# PDM.net
KiCad netlist of a schematic drawn in EAGLE
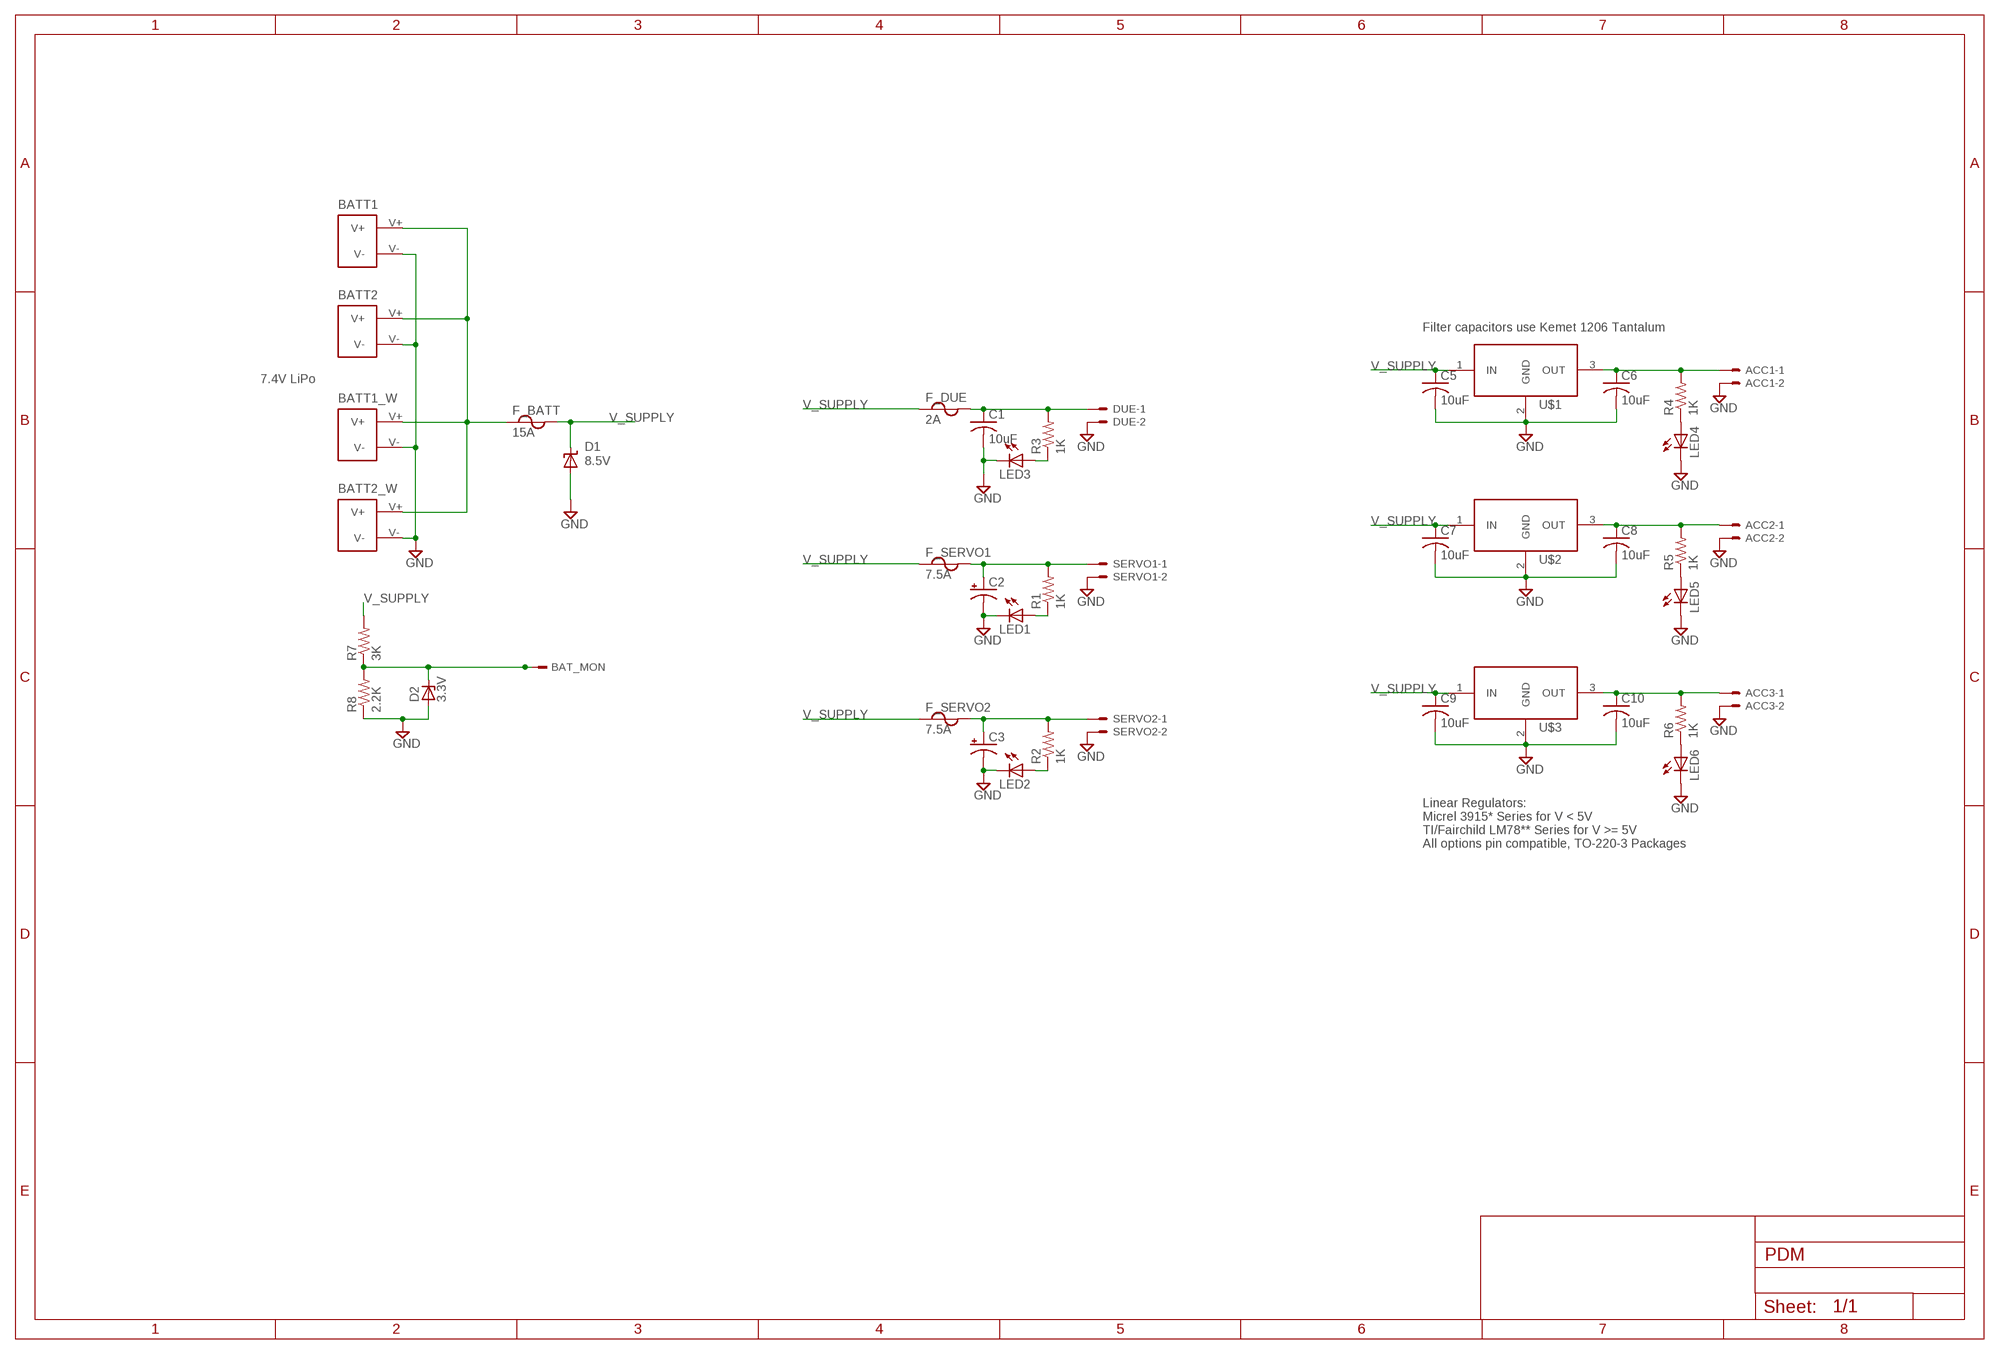
[diagram p0: schematic, sheet 1]

(export (version "E")
  (design (tool "Eeschema 10.0.6"))
  (components
    (comp (ref "ACC1")
      (value "5566-2")
      (footprint "eagle-import:5566-2")
      (libsource (lib "eagle-import") (part "5566-2"))
    )
    (comp (ref "ACC2")
      (value "5566-2")
      (footprint "eagle-import:5566-2")
      (libsource (lib "eagle-import") (part "5566-2"))
    )
    (comp (ref "ACC3")
      (value "5566-2")
      (footprint "eagle-import:5566-2")
      (libsource (lib "eagle-import") (part "5566-2"))
    )
    (comp (ref "BATT1")
      (value "CON_XT60-PCB_MOUNT")
      (footprint "eagle-import:CON_XT60_PCB_MOUNT")
      (libsource (lib "eagle-import") (part "CON_XT60-PCB_MOUNT"))
    )
    (comp (ref "BATT1_W")
      (value "CON_XT60-PIGTAIL")
      (footprint "eagle-import:CON_XT60_PIGTAIL")
      (libsource (lib "eagle-import") (part "CON_XT60-PIGTAIL"))
    )
    (comp (ref "BATT2")
      (value "CON_XT60-PCB_MOUNT")
      (footprint "eagle-import:CON_XT60_PCB_MOUNT")
      (libsource (lib "eagle-import") (part "CON_XT60-PCB_MOUNT"))
    )
    (comp (ref "BATT2_W")
      (value "CON_XT60-PIGTAIL")
      (footprint "eagle-import:CON_XT60_PIGTAIL")
      (libsource (lib "eagle-import") (part "CON_XT60-PIGTAIL"))
    )
    (comp (ref "BAT_MON")
      (value "TSW-101-02-S-S")
      (footprint "eagle-import:TSW-101-02-S-S")
      (libsource (lib "eagle-import") (part "TSW-101-02-S-S"))
    )
    (comp (ref "C1")
      (value "10uF")
      (footprint "eagle-import:C1206K")
      (libsource (lib "eagle-import") (part "C-USC1206K"))
    )
    (comp (ref "C2")
      (value "CPOL-USTT5D11")
      (footprint "eagle-import:TT5D11")
      (libsource (lib "eagle-import") (part "CPOL-USTT5D11"))
    )
    (comp (ref "C3")
      (value "CPOL-USTT5D11")
      (footprint "eagle-import:TT5D11")
      (libsource (lib "eagle-import") (part "CPOL-USTT5D11"))
    )
    (comp (ref "C5")
      (value "10uF")
      (footprint "eagle-import:C1206K")
      (libsource (lib "eagle-import") (part "C-USC1206K"))
    )
    (comp (ref "C6")
      (value "10uF")
      (footprint "eagle-import:C1206K")
      (libsource (lib "eagle-import") (part "C-USC1206K"))
    )
    (comp (ref "C7")
      (value "10uF")
      (footprint "eagle-import:C1206K")
      (libsource (lib "eagle-import") (part "C-USC1206K"))
    )
    (comp (ref "C8")
      (value "10uF")
      (footprint "eagle-import:C1206K")
      (libsource (lib "eagle-import") (part "C-USC1206K"))
    )
    (comp (ref "C9")
      (value "10uF")
      (footprint "eagle-import:C1206K")
      (libsource (lib "eagle-import") (part "C-USC1206K"))
    )
    (comp (ref "C10")
      (value "10uF")
      (footprint "eagle-import:C1206K")
      (libsource (lib "eagle-import") (part "C-USC1206K"))
    )
    (comp (ref "D1")
      (value "8.5V")
      (footprint "eagle-import:SMBJ")
      (libsource (lib "eagle-import") (part "SUPPRESSOR-SMBJ"))
    )
    (comp (ref "D2")
      (value "3.3V")
      (footprint "eagle-import:SMB")
      (libsource (lib "eagle-import") (part "ZENER-DIODESMB"))
    )
    (comp (ref "DUE")
      (value "5566-2")
      (footprint "eagle-import:5566-2")
      (libsource (lib "eagle-import") (part "5566-2"))
    )
    (comp (ref "F_BATT")
      (value "15A")
      (footprint "eagle-import:ATO")
      (libsource (lib "eagle-import") (part "FUSE-ATO"))
    )
    (comp (ref "F_DUE")
      (value "2A")
      (footprint "eagle-import:ATO")
      (libsource (lib "eagle-import") (part "FUSE-ATO"))
    )
    (comp (ref "F_SERVO1")
      (value "7.5A")
      (footprint "eagle-import:ATO")
      (libsource (lib "eagle-import") (part "FUSE-ATO"))
    )
    (comp (ref "F_SERVO2")
      (value "7.5A")
      (footprint "eagle-import:ATO")
      (libsource (lib "eagle-import") (part "FUSE-ATO"))
    )
    (comp (ref "LED1")
      (value "LEDSML1206")
      (footprint "eagle-import:SML1206")
      (libsource (lib "eagle-import") (part "LEDSML1206"))
    )
    (comp (ref "LED2")
      (value "LEDSML1206")
      (footprint "eagle-import:SML1206")
      (libsource (lib "eagle-import") (part "LEDSML1206"))
    )
    (comp (ref "LED3")
      (value "LEDSML1206")
      (footprint "eagle-import:SML1206")
      (libsource (lib "eagle-import") (part "LEDSML1206"))
    )
    (comp (ref "LED4")
      (value "LEDSML1206")
      (footprint "eagle-import:SML1206")
      (libsource (lib "eagle-import") (part "LEDSML1206"))
    )
    (comp (ref "LED5")
      (value "LEDSML1206")
      (footprint "eagle-import:SML1206")
      (libsource (lib "eagle-import") (part "LEDSML1206"))
    )
    (comp (ref "LED6")
      (value "LEDSML1206")
      (footprint "eagle-import:SML1206")
      (libsource (lib "eagle-import") (part "LEDSML1206"))
    )
    (comp (ref "R1")
      (value "1K")
      (footprint "eagle-import:R1206")
      (libsource (lib "eagle-import") (part "R-US_R1206"))
    )
    (comp (ref "R2")
      (value "1K")
      (footprint "eagle-import:R1206")
      (libsource (lib "eagle-import") (part "R-US_R1206"))
    )
    (comp (ref "R3")
      (value "1K")
      (footprint "eagle-import:R1206")
      (libsource (lib "eagle-import") (part "R-US_R1206"))
    )
    (comp (ref "R4")
      (value "1K")
      (footprint "eagle-import:R1206")
      (libsource (lib "eagle-import") (part "R-US_R1206"))
    )
    (comp (ref "R5")
      (value "1K")
      (footprint "eagle-import:R1206")
      (libsource (lib "eagle-import") (part "R-US_R1206"))
    )
    (comp (ref "R6")
      (value "1K")
      (footprint "eagle-import:R1206")
      (libsource (lib "eagle-import") (part "R-US_R1206"))
    )
    (comp (ref "R7")
      (value "3K")
      (footprint "eagle-import:R1206")
      (libsource (lib "eagle-import") (part "R-US_R1206"))
    )
    (comp (ref "R8")
      (value "2.2K")
      (footprint "eagle-import:R1206")
      (libsource (lib "eagle-import") (part "R-US_R1206"))
    )
    (comp (ref "SERVO1")
      (value "5566-2")
      (footprint "eagle-import:5566-2")
      (libsource (lib "eagle-import") (part "5566-2"))
    )
    (comp (ref "SERVO2")
      (value "5566-2")
      (footprint "eagle-import:5566-2")
      (libsource (lib "eagle-import") (part "5566-2"))
    )
    (comp (ref "U$1")
      (value "MIC29150/29300/29500VERTICAL")
      (footprint "eagle-import:TO220V")
      (libsource (lib "eagle-import") (part "MIC29150/29300/29500VERTICAL"))
    )
    (comp (ref "U$2")
      (value "MIC29150/29300/29500VERTICAL")
      (footprint "eagle-import:TO220V")
      (libsource (lib "eagle-import") (part "MIC29150/29300/29500VERTICAL"))
    )
    (comp (ref "U$3")
      (value "MIC29150/29300/29500VERTICAL")
      (footprint "eagle-import:TO220V")
      (libsource (lib "eagle-import") (part "MIC29150/29300/29500VERTICAL"))
    )
  )
  (nets
    (net (code "1") (name "/V_SUPPLY") (class "Default")
      (node (ref "C5") (pin "1") (pinfunction "1_1") (pintype "passive"))
      (node (ref "C7") (pin "1") (pinfunction "1_1") (pintype "passive"))
      (node (ref "C9") (pin "1") (pinfunction "1_1") (pintype "passive"))
      (node (ref "D1") (pin "C") (pinfunction "C_C") (pintype "passive"))
      (node (ref "F_BATT") (pin "B1") (pinfunction "2_B1") (pintype "passive"))
      (node (ref "F_BATT") (pin "B2") (pinfunction "2_B2") (pintype "passive"))
      (node (ref "F_BATT") (pin "B3") (pinfunction "2_B3") (pintype "passive"))
      (node (ref "F_BATT") (pin "B4") (pinfunction "2_B4") (pintype "passive"))
      (node (ref "F_DUE") (pin "A1") (pinfunction "1_A1") (pintype "passive"))
      (node (ref "F_DUE") (pin "A2") (pinfunction "1_A2") (pintype "passive"))
      (node (ref "F_DUE") (pin "A3") (pinfunction "1_A3") (pintype "passive"))
      (node (ref "F_DUE") (pin "A4") (pinfunction "1_A4") (pintype "passive"))
      (node (ref "F_SERVO1") (pin "A1") (pinfunction "1_A1") (pintype "passive"))
      (node (ref "F_SERVO1") (pin "A2") (pinfunction "1_A2") (pintype "passive"))
      (node (ref "F_SERVO1") (pin "A3") (pinfunction "1_A3") (pintype "passive"))
      (node (ref "F_SERVO1") (pin "A4") (pinfunction "1_A4") (pintype "passive"))
      (node (ref "F_SERVO2") (pin "A1") (pinfunction "1_A1") (pintype "passive"))
      (node (ref "F_SERVO2") (pin "A2") (pinfunction "1_A2") (pintype "passive"))
      (node (ref "F_SERVO2") (pin "A3") (pinfunction "1_A3") (pintype "passive"))
      (node (ref "F_SERVO2") (pin "A4") (pinfunction "1_A4") (pintype "passive"))
      (node (ref "R7") (pin "2") (pinfunction "2_2") (pintype "passive"))
      (node (ref "U$1") (pin "1") (pinfunction "IN_1") (pintype "bidirectional"))
      (node (ref "U$2") (pin "1") (pinfunction "IN_1") (pintype "bidirectional"))
      (node (ref "U$3") (pin "1") (pinfunction "IN_1") (pintype "bidirectional"))
    )
    (net (code "2") (name "GND") (class "Default")
      (node (ref "ACC1") (pin "2") (pinfunction "S_2") (pintype "passive"))
      (node (ref "ACC2") (pin "2") (pinfunction "S_2") (pintype "passive"))
      (node (ref "ACC3") (pin "2") (pinfunction "S_2") (pintype "passive"))
      (node (ref "BATT1") (pin "V-") (pinfunction "V-_V-") (pintype "bidirectional"))
      (node (ref "BATT1_W") (pin "V-") (pinfunction "V-_V-") (pintype "bidirectional"))
      (node (ref "BATT2") (pin "V-") (pinfunction "V-_V-") (pintype "bidirectional"))
      (node (ref "BATT2_W") (pin "V-") (pinfunction "V-_V-") (pintype "bidirectional"))
      (node (ref "C1") (pin "2") (pinfunction "2_2") (pintype "passive"))
      (node (ref "C10") (pin "2") (pinfunction "2_2") (pintype "passive"))
      (node (ref "C2") (pin "-") (pinfunction "-_-") (pintype "passive"))
      (node (ref "C3") (pin "-") (pinfunction "-_-") (pintype "passive"))
      (node (ref "C5") (pin "2") (pinfunction "2_2") (pintype "passive"))
      (node (ref "C6") (pin "2") (pinfunction "2_2") (pintype "passive"))
      (node (ref "C7") (pin "2") (pinfunction "2_2") (pintype "passive"))
      (node (ref "C8") (pin "2") (pinfunction "2_2") (pintype "passive"))
      (node (ref "C9") (pin "2") (pinfunction "2_2") (pintype "passive"))
      (node (ref "D1") (pin "A") (pinfunction "A_A") (pintype "passive"))
      (node (ref "D2") (pin "A") (pinfunction "A_A") (pintype "passive"))
      (node (ref "DUE") (pin "2") (pinfunction "S_2") (pintype "passive"))
      (node (ref "LED1") (pin "C") (pinfunction "C_C") (pintype "passive"))
      (node (ref "LED2") (pin "C") (pinfunction "C_C") (pintype "passive"))
      (node (ref "LED3") (pin "C") (pinfunction "C_C") (pintype "passive"))
      (node (ref "LED4") (pin "C") (pinfunction "C_C") (pintype "passive"))
      (node (ref "LED5") (pin "C") (pinfunction "C_C") (pintype "passive"))
      (node (ref "LED6") (pin "C") (pinfunction "C_C") (pintype "passive"))
      (node (ref "R8") (pin "1") (pinfunction "1_1") (pintype "passive"))
      (node (ref "SERVO1") (pin "2") (pinfunction "S_2") (pintype "passive"))
      (node (ref "SERVO2") (pin "2") (pinfunction "S_2") (pintype "passive"))
      (node (ref "U$1") (pin "2") (pinfunction "GND_2") (pintype "bidirectional"))
      (node (ref "U$2") (pin "2") (pinfunction "GND_2") (pintype "bidirectional"))
      (node (ref "U$3") (pin "2") (pinfunction "GND_2") (pintype "bidirectional"))
    )
    (net (code "3") (name "Net-(ACC1A-S)") (class "Default")
      (node (ref "ACC1") (pin "1") (pinfunction "S_1") (pintype "passive"))
      (node (ref "C6") (pin "1") (pinfunction "1_1") (pintype "passive"))
      (node (ref "R4") (pin "2") (pinfunction "2_2") (pintype "passive"))
      (node (ref "U$1") (pin "3") (pinfunction "OUT_3") (pintype "bidirectional"))
    )
    (net (code "4") (name "Net-(ACC2A-S)") (class "Default")
      (node (ref "ACC2") (pin "1") (pinfunction "S_1") (pintype "passive"))
      (node (ref "C8") (pin "1") (pinfunction "1_1") (pintype "passive"))
      (node (ref "R5") (pin "2") (pinfunction "2_2") (pintype "passive"))
      (node (ref "U$2") (pin "3") (pinfunction "OUT_3") (pintype "bidirectional"))
    )
    (net (code "5") (name "Net-(ACC3A-S)") (class "Default")
      (node (ref "ACC3") (pin "1") (pinfunction "S_1") (pintype "passive"))
      (node (ref "C10") (pin "1") (pinfunction "1_1") (pintype "passive"))
      (node (ref "R6") (pin "2") (pinfunction "2_2") (pintype "passive"))
      (node (ref "U$3") (pin "3") (pinfunction "OUT_3") (pintype "bidirectional"))
    )
    (net (code "6") (name "Net-(BATT1-PadV+)") (class "Default")
      (node (ref "BATT1") (pin "V+") (pinfunction "V+_V+") (pintype "bidirectional"))
      (node (ref "BATT1_W") (pin "V+") (pinfunction "V+_V+") (pintype "bidirectional"))
      (node (ref "BATT2") (pin "V+") (pinfunction "V+_V+") (pintype "bidirectional"))
      (node (ref "BATT2_W") (pin "V+") (pinfunction "V+_V+") (pintype "bidirectional"))
      (node (ref "F_BATT") (pin "A1") (pinfunction "1_A1") (pintype "passive"))
      (node (ref "F_BATT") (pin "A2") (pinfunction "1_A2") (pintype "passive"))
      (node (ref "F_BATT") (pin "A3") (pinfunction "1_A3") (pintype "passive"))
      (node (ref "F_BATT") (pin "A4") (pinfunction "1_A4") (pintype "passive"))
    )
    (net (code "7") (name "Net-(BAT_MON-Pad1)") (class "Default")
      (node (ref "BAT_MON") (pin "1") (pinfunction "1_1") (pintype "passive"))
      (node (ref "D2") (pin "C") (pinfunction "C_C") (pintype "passive"))
      (node (ref "R7") (pin "1") (pinfunction "1_1") (pintype "passive"))
      (node (ref "R8") (pin "2") (pinfunction "2_2") (pintype "passive"))
    )
    (net (code "8") (name "Net-(DUEA-S)") (class "Default")
      (node (ref "C1") (pin "1") (pinfunction "1_1") (pintype "passive"))
      (node (ref "DUE") (pin "1") (pinfunction "S_1") (pintype "passive"))
      (node (ref "F_DUE") (pin "B1") (pinfunction "2_B1") (pintype "passive"))
      (node (ref "F_DUE") (pin "B2") (pinfunction "2_B2") (pintype "passive"))
      (node (ref "F_DUE") (pin "B3") (pinfunction "2_B3") (pintype "passive"))
      (node (ref "F_DUE") (pin "B4") (pinfunction "2_B4") (pintype "passive"))
      (node (ref "R3") (pin "2") (pinfunction "2_2") (pintype "passive"))
    )
    (net (code "9") (name "Net-(LED1-PadA)") (class "Default")
      (node (ref "LED1") (pin "A") (pinfunction "A_A") (pintype "passive"))
      (node (ref "R1") (pin "1") (pinfunction "1_1") (pintype "passive"))
    )
    (net (code "10") (name "Net-(LED2-PadA)") (class "Default")
      (node (ref "LED2") (pin "A") (pinfunction "A_A") (pintype "passive"))
      (node (ref "R2") (pin "1") (pinfunction "1_1") (pintype "passive"))
    )
    (net (code "11") (name "Net-(LED3-PadA)") (class "Default")
      (node (ref "LED3") (pin "A") (pinfunction "A_A") (pintype "passive"))
      (node (ref "R3") (pin "1") (pinfunction "1_1") (pintype "passive"))
    )
    (net (code "12") (name "Net-(LED4-PadA)") (class "Default")
      (node (ref "LED4") (pin "A") (pinfunction "A_A") (pintype "passive"))
      (node (ref "R4") (pin "1") (pinfunction "1_1") (pintype "passive"))
    )
    (net (code "13") (name "Net-(LED5-PadA)") (class "Default")
      (node (ref "LED5") (pin "A") (pinfunction "A_A") (pintype "passive"))
      (node (ref "R5") (pin "1") (pinfunction "1_1") (pintype "passive"))
    )
    (net (code "14") (name "Net-(LED6-PadA)") (class "Default")
      (node (ref "LED6") (pin "A") (pinfunction "A_A") (pintype "passive"))
      (node (ref "R6") (pin "1") (pinfunction "1_1") (pintype "passive"))
    )
    (net (code "15") (name "Net-(SERVO1A-S)") (class "Default")
      (node (ref "C2") (pin "+") (pinfunction "+_+") (pintype "passive"))
      (node (ref "F_SERVO1") (pin "B1") (pinfunction "2_B1") (pintype "passive"))
      (node (ref "F_SERVO1") (pin "B2") (pinfunction "2_B2") (pintype "passive"))
      (node (ref "F_SERVO1") (pin "B3") (pinfunction "2_B3") (pintype "passive"))
      (node (ref "F_SERVO1") (pin "B4") (pinfunction "2_B4") (pintype "passive"))
      (node (ref "R1") (pin "2") (pinfunction "2_2") (pintype "passive"))
      (node (ref "SERVO1") (pin "1") (pinfunction "S_1") (pintype "passive"))
    )
    (net (code "16") (name "Net-(SERVO2A-S)") (class "Default")
      (node (ref "C3") (pin "+") (pinfunction "+_+") (pintype "passive"))
      (node (ref "F_SERVO2") (pin "B1") (pinfunction "2_B1") (pintype "passive"))
      (node (ref "F_SERVO2") (pin "B2") (pinfunction "2_B2") (pintype "passive"))
      (node (ref "F_SERVO2") (pin "B3") (pinfunction "2_B3") (pintype "passive"))
      (node (ref "F_SERVO2") (pin "B4") (pinfunction "2_B4") (pintype "passive"))
      (node (ref "R2") (pin "2") (pinfunction "2_2") (pintype "passive"))
      (node (ref "SERVO2") (pin "1") (pinfunction "S_1") (pintype "passive"))
    )
  )
)
